# schematic.net
KiCad netlist of a schematic drawn in Altium Designer
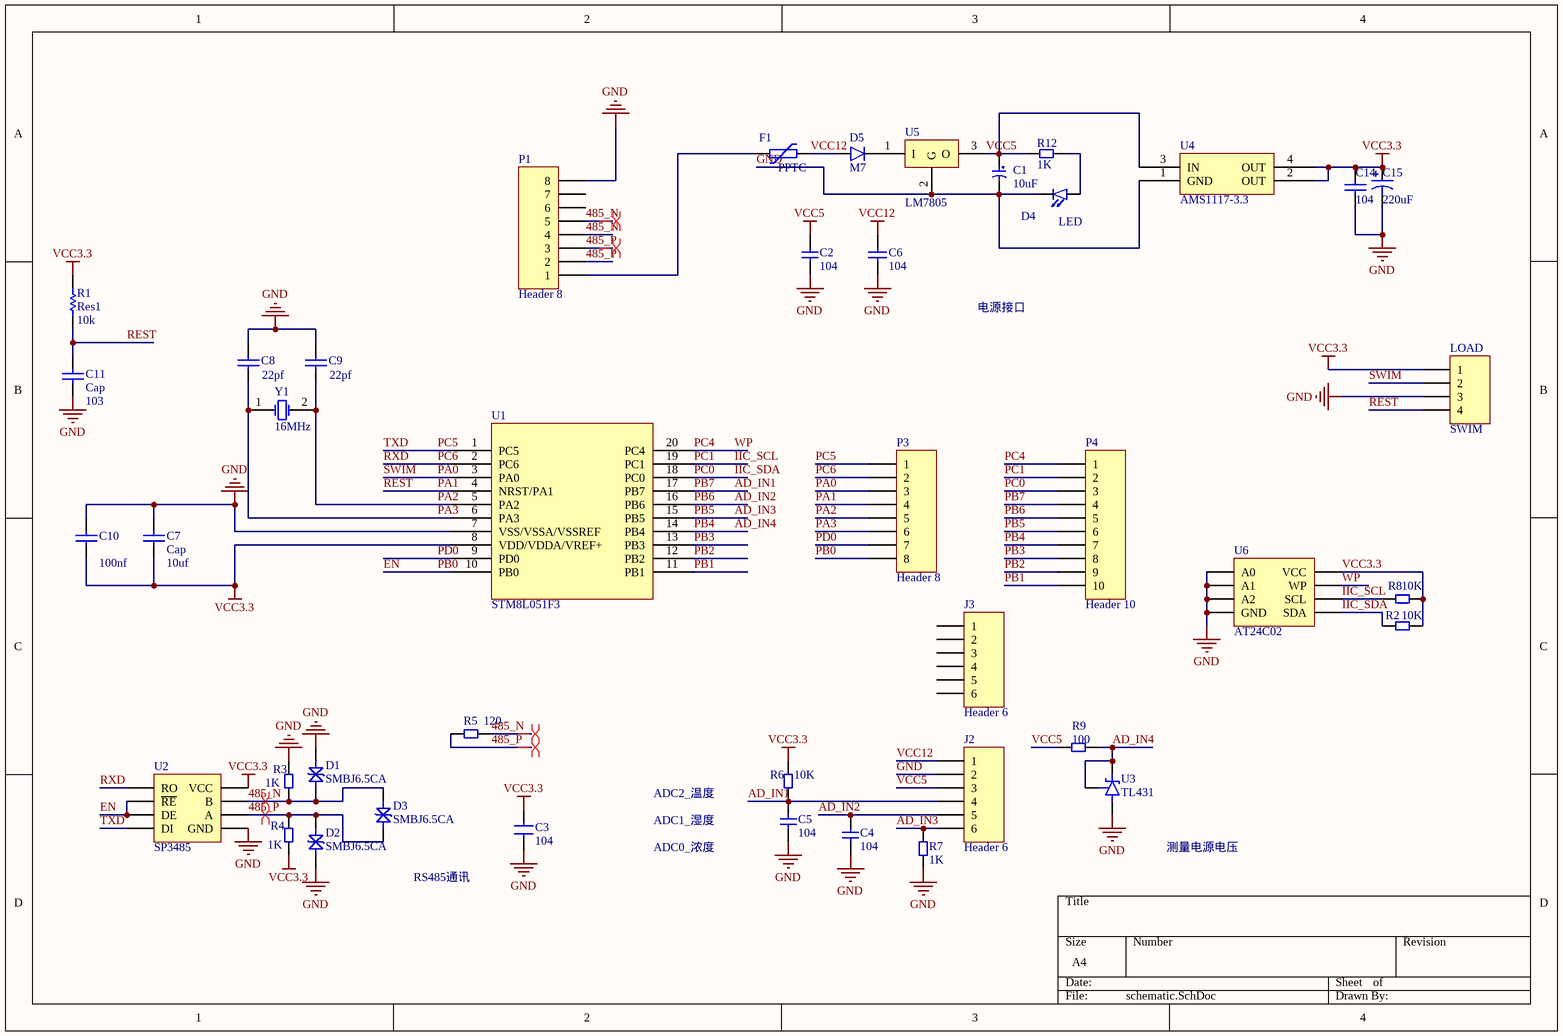
[diagram p0: schematic.SchDoc]

(export (version "E")
  (design (tool "Eeschema 10.0.6"))
  (components
    (comp (ref "C1") (value "10uF") (footprint "1206-d") (libsource (lib "基本") (part "CAP-POL")))
    (comp (ref "C2") (value "104") (footprint "0805") (libsource (lib "基本") (part "CAP")))
    (comp (ref "C3") (value "104") (footprint "0805") (libsource (lib "基本") (part "Cap")))
    (comp (ref "C4") (value "104") (footprint "0805") (libsource (lib "基本") (part "CAP")))
    (comp (ref "C5") (value "104") (footprint "0805") (libsource (lib "基本") (part "CAP")))
    (comp (ref "C6") (value "104") (footprint "0805C") (libsource (lib "basic") (part "CAP")))
    (comp (ref "C7")
      (value "Cap")
      (footprint "1206-D")
      (description "Capacitor")
      (fields (field (name "ALTIUM_VALUE") "10uf") (field (name "PUBLISHER") "Altium Limited"))
      (libsource (lib "Miscellaneous Devices") (part "Cap"))
    )
    (comp (ref "C8")
      (value "22pf")
      (footprint "6-0805_N")
      (description "Capacitor")
      (fields (field (name "Comment") "Cap") (field (name "PUBLISHER") "Altium Limited"))
      (libsource (lib "Miscellaneous Devices") (part "Cap"))
    )
    (comp (ref "C9")
      (value "22pf")
      (footprint "6-0805_N")
      (description "Capacitor")
      (fields (field (name "Comment") "Cap") (field (name "PUBLISHER") "Altium Limited"))
      (libsource (lib "Miscellaneous Devices") (part "Cap"))
    )
    (comp (ref "C10")
      (value "100nf")
      (footprint "0805")
      (description "Capacitor")
      (fields (field (name "Comment") "Cap") (field (name "PUBLISHER") "Altium Limited"))
      (libsource (lib "Miscellaneous Devices") (part "Cap"))
    )
    (comp (ref "C11")
      (value "Cap")
      (footprint "6-0805_N")
      (description "Capacitor")
      (fields (field (name "ALTIUM_VALUE") "103") (field (name "PUBLISHER") "Altium Limited"))
      (libsource (lib "Miscellaneous Devices") (part "Cap"))
    )
    (comp (ref "C14")
      (value "104")
      (footprint "0805")
      (description "Capacitor")
      (fields (field (name "Comment") "Cap") (field (name "PUBLISHER") "Altium Limited"))
      (libsource (lib "Miscellaneous Devices") (part "Cap"))
    )
    (comp (ref "C15")
      (value "220uF")
      (footprint "1206")
      (description "Polarized Capacitor (Radial)")
      (fields (field (name "Comment") "Cap Pol1") (field (name "PUBLISHER") "Altium Limited"))
      (libsource (lib "Miscellaneous Devices") (part "Cap Pol1"))
    )
    (comp (ref "D1") (value "SMBJ6.5CA") (footprint "smb do214aa") (libsource (lib "基本") (part "SMBJ6.5CA")))
    (comp (ref "D2") (value "SMBJ6.5CA") (footprint "smb do214aa") (libsource (lib "基本") (part "SMBJ6.5CA")))
    (comp (ref "D3") (value "SMBJ6.5CA") (footprint "smb do214aa") (libsource (lib "基本") (part "SMBJ6.5CA")))
    (comp (ref "D4") (value "LED") (footprint "0805-D") (libsource (lib "基本") (part "LED")))
    (comp (ref "D5") (value "M7") (footprint "SMA (DO-214AC)") (libsource (lib "基本元件") (part "M7")))
    (comp (ref "F1") (value "PPTC") (footprint "1206") (libsource (lib "基本") (part "PPTC")))
    (comp (ref "J2")
      (value "Header 6")
      (footprint "HDR1X6")
      (description "Header, 6-Pin")
      (fields (field (name "PUBLISHER") "Altium Limited"))
      (libsource (lib "Miscellaneous Connectors") (part "Header 6"))
    )
    (comp (ref "J3")
      (value "Header 6")
      (footprint "HDR1X6")
      (description "Header, 6-Pin")
      (fields (field (name "PUBLISHER") "Altium Limited"))
      (libsource (lib "Miscellaneous Connectors") (part "Header 6"))
    )
    (comp (ref "LOAD")
      (value "SWIM")
      (footprint "HDR1X4")
      (description "Header, 4-Pin")
      (fields (field (name "PUBLISHER") "Altium Limited"))
      (libsource (lib "Miscellaneous Connectors") (part "Header 4"))
    )
    (comp (ref "P1")
      (value "Header 8")
      (footprint "RJ45")
      (description "Header, 8-Pin")
      (fields (field (name "PUBLISHER") "Altium Limited"))
      (libsource (lib "Miscellaneous Connectors") (part "Header 8"))
    )
    (comp (ref "P3")
      (value "Header 8")
      (footprint "HDR1X8")
      (description "Header, 8-Pin")
      (fields (field (name "PUBLISHER") "Altium Limited"))
      (libsource (lib "") (part "Header 8_1"))
    )
    (comp (ref "P4")
      (value "Header 10")
      (footprint "HDR1X10")
      (description "Header, 10-Pin")
      (fields (field (name "PUBLISHER") "Altium Limited"))
      (libsource (lib "Miscellaneous Connectors") (part "Header 10"))
    )
    (comp (ref "R1")
      (value "Res1")
      (footprint "6-0805_N")
      (description "Resistor")
      (fields (field (name "ALTIUM_VALUE") "10k") (field (name "PUBLISHER") "Altium Limited"))
      (libsource (lib "Miscellaneous Devices") (part "Res1"))
    )
    (comp (ref "R2") (value "10K") (footprint "0805") (libsource (lib "基本") (part "Res")))
    (comp (ref "R3") (value "1K") (footprint "0805") (libsource (lib "基本") (part "Res")))
    (comp (ref "R4") (value "1K") (footprint "0805") (libsource (lib "基本") (part "Res")))
    (comp (ref "R5") (value "120") (footprint "0805") (libsource (lib "基本") (part "Res")))
    (comp (ref "R6") (value "10K") (footprint "0805") (libsource (lib "基本") (part "Res")))
    (comp (ref "R7") (value "1K") (footprint "0805") (libsource (lib "基本") (part "Res")))
    (comp (ref "R8") (value "10K") (footprint "0805") (libsource (lib "基本") (part "Res")))
    (comp (ref "R9") (value "100") (footprint "0805") (libsource (lib "基本") (part "Res")))
    (comp (ref "R12") (value "1K") (footprint "0805") (libsource (lib "基本") (part "Res")))
    (comp (ref "U1")
      (value "STM8L051F3")
      (footprint "SOP20")
      (libsource (lib "zs_sener_lib") (part "STM8L051F3"))
    )
    (comp (ref "U2") (value "SP3485") (footprint "油烟采集模块:SOP8") (libsource (lib "常用数字芯片") (part "SP3485")))
    (comp (ref "U3") (value "TL431") (footprint "sot-23") (libsource (lib "电源类") (part "TL431")))
    (comp (ref "U4")
      (value "AMS1117-3.3")
      (footprint "SOT-223")
      (libsource (lib "AMS1117-3.3") (part "AMS1117-3.3"))
    )
    (comp (ref "U5") (value "LM7805") (footprint "to-220") (libsource (lib "电源类") (part "LM7805")))
    (comp (ref "U6") (value "AT24C02") (footprint "油烟采集模块:sop8") (libsource (lib "常用数字芯片") (part "AT24C02")))
    (comp (ref "Y1")
      (value "16MHz")
      (footprint "Y2")
      (description "Crystal Oscillator")
      (fields (field (name "PUBLISHER") "Altium Limited"))
      (libsource (lib "Miscellaneous Devices") (part "XTAL"))
    )
  )
  (nets
    (net (code "1") (name "/485_N") (class "Default")
      (node (ref "D1") (pin "2") (pinfunction "2_2") (pintype "passive"))
      (node (ref "D3") (pin "1") (pinfunction "1_1") (pintype "passive"))
      (node (ref "P1") (pin "4") (pinfunction "4_4") (pintype "passive"))
      (node (ref "P1") (pin "5") (pinfunction "5_5") (pintype "passive"))
      (node (ref "R3") (pin "1") (pinfunction "1_1") (pintype "passive"))
      (node (ref "R5") (pin "1") (pinfunction "1_1") (pintype "passive"))
      (node (ref "U2") (pin "7") (pinfunction "B_7") (pintype "passive"))
    )
    (net (code "2") (name "/485_P") (class "Default")
      (node (ref "D2") (pin "1") (pinfunction "1_1") (pintype "passive"))
      (node (ref "D3") (pin "2") (pinfunction "2_2") (pintype "passive"))
      (node (ref "P1") (pin "2") (pinfunction "2_2") (pintype "passive"))
      (node (ref "P1") (pin "3") (pinfunction "3_3") (pintype "passive"))
      (node (ref "R4") (pin "2") (pinfunction "2_2") (pintype "passive"))
      (node (ref "R5") (pin "2") (pinfunction "2_2") (pintype "passive"))
      (node (ref "U2") (pin "6") (pinfunction "A_6") (pintype "passive"))
    )
    (net (code "3") (name "/AD_IN1") (class "Default")
      (node (ref "C5") (pin "2") (pinfunction "2_2") (pintype "passive"))
      (node (ref "J2") (pin "4") (pinfunction "4_4") (pintype "passive"))
      (node (ref "P4") (pin "4") (pinfunction "4_4") (pintype "passive"))
      (node (ref "R6") (pin "1") (pinfunction "1_1") (pintype "passive"))
      (node (ref "U1") (pin "17") (pinfunction "PB7_17") (pintype "passive"))
    )
    (net (code "4") (name "/AD_IN2") (class "Default")
      (node (ref "C4") (pin "2") (pinfunction "2_2") (pintype "passive"))
      (node (ref "J2") (pin "5") (pinfunction "5_5") (pintype "passive"))
      (node (ref "P4") (pin "5") (pinfunction "5_5") (pintype "passive"))
      (node (ref "U1") (pin "16") (pinfunction "PB6_16") (pintype "passive"))
    )
    (net (code "5") (name "/AD_IN3") (class "Default")
      (node (ref "J2") (pin "6") (pinfunction "6_6") (pintype "passive"))
      (node (ref "P4") (pin "6") (pinfunction "6_6") (pintype "passive"))
      (node (ref "R7") (pin "2") (pinfunction "2_2") (pintype "passive"))
      (node (ref "U1") (pin "15") (pinfunction "PB5_15") (pintype "passive"))
    )
    (net (code "6") (name "/AD_IN4") (class "Default")
      (node (ref "P4") (pin "7") (pinfunction "7_7") (pintype "passive"))
      (node (ref "R9") (pin "2") (pinfunction "2_2") (pintype "passive"))
      (node (ref "U1") (pin "14") (pinfunction "PB4_14") (pintype "passive"))
      (node (ref "U3") (pin "1") (pinfunction "1_1") (pintype "passive"))
      (node (ref "U3") (pin "2") (pinfunction "2_2") (pintype "passive"))
    )
    (net (code "7") (name "/EN") (class "Default")
      (node (ref "P3") (pin "8") (pinfunction "8_8") (pintype "passive"))
      (node (ref "U1") (pin "10") (pinfunction "PB0_10") (pintype "passive"))
      (node (ref "U2") (pin "2") (pinfunction "~{RE}_2") (pintype "passive"))
      (node (ref "U2") (pin "3") (pinfunction "DE_3") (pintype "passive"))
    )
    (net (code "8") (name "/IIC_SCL") (class "Default")
      (node (ref "P4") (pin "2") (pinfunction "2_2") (pintype "passive"))
      (node (ref "R8") (pin "1") (pinfunction "1_1") (pintype "passive"))
      (node (ref "U1") (pin "19") (pinfunction "PC1_19") (pintype "passive"))
      (node (ref "U6") (pin "6") (pinfunction "SCL_6") (pintype "passive"))
    )
    (net (code "9") (name "/IIC_SDA") (class "Default")
      (node (ref "P4") (pin "3") (pinfunction "3_3") (pintype "passive"))
      (node (ref "R2") (pin "1") (pinfunction "1_1") (pintype "passive"))
      (node (ref "U1") (pin "18") (pinfunction "PC0_18") (pintype "passive"))
      (node (ref "U6") (pin "5") (pinfunction "SDA_5") (pintype "passive"))
    )
    (net (code "10") (name "/PA0") (class "Default")
      (node (ref "LOAD") (pin "2") (pinfunction "2_2") (pintype "passive"))
      (node (ref "P3") (pin "3") (pinfunction "3_3") (pintype "passive"))
      (node (ref "U1") (pin "3") (pinfunction "PA0_3") (pintype "passive"))
    )
    (net (code "11") (name "/PA1") (class "Default")
      (node (ref "C11") (pin "2") (pinfunction "2_2") (pintype "passive"))
      (node (ref "LOAD") (pin "4") (pinfunction "4_4") (pintype "passive"))
      (node (ref "P3") (pin "4") (pinfunction "4_4") (pintype "passive"))
      (node (ref "R1") (pin "1") (pinfunction "1_1") (pintype "passive"))
      (node (ref "U1") (pin "4") (pinfunction "NRST/PA1_4") (pintype "passive"))
    )
    (net (code "12") (name "/PA2") (class "Default")
      (node (ref "C9") (pin "2") (pinfunction "2_2") (pintype "passive"))
      (node (ref "P3") (pin "5") (pinfunction "5_5") (pintype "passive"))
      (node (ref "U1") (pin "5") (pinfunction "PA2_5") (pintype "passive"))
      (node (ref "Y1") (pin "2") (pinfunction "OSC2_2") (pintype "passive"))
    )
    (net (code "13") (name "/PA3") (class "Default")
      (node (ref "C8") (pin "1") (pinfunction "1_1") (pintype "passive"))
      (node (ref "P3") (pin "6") (pinfunction "6_6") (pintype "passive"))
      (node (ref "U1") (pin "6") (pinfunction "PA3_6") (pintype "passive"))
      (node (ref "Y1") (pin "1") (pinfunction "OSC1_1") (pintype "passive"))
    )
    (net (code "14") (name "/PB1") (class "Default")
      (node (ref "P4") (pin "10") (pinfunction "10_10") (pintype "passive"))
      (node (ref "U1") (pin "11") (pinfunction "PB1_11") (pintype "passive"))
    )
    (net (code "15") (name "/PB2") (class "Default")
      (node (ref "P4") (pin "9") (pinfunction "9_9") (pintype "passive"))
      (node (ref "U1") (pin "12") (pinfunction "PB2_12") (pintype "passive"))
    )
    (net (code "16") (name "/PB3") (class "Default")
      (node (ref "P4") (pin "8") (pinfunction "8_8") (pintype "passive"))
      (node (ref "U1") (pin "13") (pinfunction "PB3_13") (pintype "passive"))
    )
    (net (code "17") (name "/PC4") (class "Default")
      (node (ref "P4") (pin "1") (pinfunction "1_1") (pintype "passive"))
      (node (ref "U1") (pin "20") (pinfunction "PC4_20") (pintype "passive"))
      (node (ref "U6") (pin "7") (pinfunction "WP_7") (pintype "passive"))
    )
    (net (code "18") (name "/PC5") (class "Default")
      (node (ref "P3") (pin "1") (pinfunction "1_1") (pintype "passive"))
      (node (ref "U1") (pin "1") (pinfunction "PC5_1") (pintype "passive"))
      (node (ref "U2") (pin "4") (pinfunction "DI_4") (pintype "passive"))
    )
    (net (code "19") (name "/PC6") (class "Default")
      (node (ref "P3") (pin "2") (pinfunction "2_2") (pintype "passive"))
      (node (ref "U1") (pin "2") (pinfunction "PC6_2") (pintype "passive"))
      (node (ref "U2") (pin "1") (pinfunction "RO_1") (pintype "passive"))
    )
    (net (code "20") (name "/PD0") (class "Default")
      (node (ref "P3") (pin "7") (pinfunction "7_7") (pintype "passive"))
      (node (ref "U1") (pin "9") (pinfunction "PD0_9") (pintype "passive"))
    )
    (net (code "21") (name "GND") (class "Default")
      (node (ref "C1") (pin "1") (pinfunction "1_1") (pintype "passive"))
      (node (ref "C10") (pin "2") (pinfunction "2_2") (pintype "passive"))
      (node (ref "C11") (pin "1") (pinfunction "1_1") (pintype "passive"))
      (node (ref "C14") (pin "1") (pinfunction "1_1") (pintype "passive"))
      (node (ref "C15") (pin "2") (pinfunction "2_2") (pintype "passive"))
      (node (ref "C2") (pin "1") (pinfunction "1_1") (pintype "passive"))
      (node (ref "C3") (pin "1") (pinfunction "1_1") (pintype "passive"))
      (node (ref "C4") (pin "1") (pinfunction "1_1") (pintype "passive"))
      (node (ref "C5") (pin "1") (pinfunction "1_1") (pintype "passive"))
      (node (ref "C6") (pin "1") (pinfunction "1_1") (pintype "passive"))
      (node (ref "C7") (pin "1") (pinfunction "1_1") (pintype "passive"))
      (node (ref "C8") (pin "2") (pinfunction "2_2") (pintype "passive"))
      (node (ref "C9") (pin "1") (pinfunction "1_1") (pintype "passive"))
      (node (ref "D1") (pin "1") (pinfunction "1_1") (pintype "passive"))
      (node (ref "D2") (pin "2") (pinfunction "2_2") (pintype "passive"))
      (node (ref "D4") (pin "2") (pinfunction "2_2") (pintype "passive"))
      (node (ref "J2") (pin "2") (pinfunction "2_2") (pintype "passive"))
      (node (ref "LOAD") (pin "3") (pinfunction "3_3") (pintype "passive"))
      (node (ref "P1") (pin "8") (pinfunction "8_8") (pintype "passive"))
      (node (ref "R3") (pin "2") (pinfunction "2_2") (pintype "passive"))
      (node (ref "R7") (pin "1") (pinfunction "1_1") (pintype "passive"))
      (node (ref "U1") (pin "7") (pinfunction "VSS/VSSA/VSSREF_7") (pintype "passive"))
      (node (ref "U2") (pin "5") (pinfunction "GND_5") (pintype "passive"))
      (node (ref "U3") (pin "3") (pinfunction "3_3") (pintype "passive"))
      (node (ref "U4") (pin "1") (pinfunction "GND_1") (pintype "passive"))
      (node (ref "U5") (pin "2") (pinfunction "G_2") (pintype "passive"))
      (node (ref "U6") (pin "1") (pinfunction "A0_1") (pintype "passive"))
      (node (ref "U6") (pin "2") (pinfunction "A1_2") (pintype "passive"))
      (node (ref "U6") (pin "3") (pinfunction "A2_3") (pintype "passive"))
      (node (ref "U6") (pin "4") (pinfunction "GND_4") (pintype "passive"))
    )
    (net (code "22") (name "Net-(D4-Pad1)") (class "Default")
      (node (ref "D4") (pin "1") (pinfunction "1_1") (pintype "passive"))
      (node (ref "R12") (pin "2") (pinfunction "2_2") (pintype "passive"))
    )
    (net (code "23") (name "Net-(D5--)") (class "Default")
      (node (ref "D5") (pin "1") (pinfunction "-_1") (pintype "passive"))
      (node (ref "U5") (pin "1") (pinfunction "I_1") (pintype "passive"))
    )
    (net (code "24") (name "Net-(F1-Pad1)") (class "Default")
      (node (ref "F1") (pin "1") (pinfunction "1_1") (pintype "passive"))
      (node (ref "P1") (pin "1") (pinfunction "1_1") (pintype "passive"))
    )
    (net (code "25") (name "VCC3.3") (class "Default")
      (node (ref "C10") (pin "1") (pinfunction "1_1") (pintype "passive"))
      (node (ref "C14") (pin "2") (pinfunction "2_2") (pintype "passive"))
      (node (ref "C15") (pin "1") (pinfunction "1_1") (pintype "passive"))
      (node (ref "C3") (pin "2") (pinfunction "2_2") (pintype "passive"))
      (node (ref "C7") (pin "2") (pinfunction "2_2") (pintype "passive"))
      (node (ref "LOAD") (pin "1") (pinfunction "1_1") (pintype "passive"))
      (node (ref "R1") (pin "2") (pinfunction "2_2") (pintype "passive"))
      (node (ref "R2") (pin "2") (pinfunction "2_2") (pintype "passive"))
      (node (ref "R4") (pin "1") (pinfunction "1_1") (pintype "passive"))
      (node (ref "R6") (pin "2") (pinfunction "2_2") (pintype "passive"))
      (node (ref "R8") (pin "2") (pinfunction "2_2") (pintype "passive"))
      (node (ref "U1") (pin "8") (pinfunction "VDD/VDDA/VREF+_8") (pintype "passive"))
      (node (ref "U2") (pin "8") (pinfunction "VCC_8") (pintype "passive"))
      (node (ref "U4") (pin "2") (pinfunction "OUT_2") (pintype "passive"))
      (node (ref "U4") (pin "4") (pinfunction "OUT_4") (pintype "passive"))
      (node (ref "U6") (pin "8") (pinfunction "VCC_8") (pintype "passive"))
    )
    (net (code "26") (name "VCC5") (class "Default")
      (node (ref "C1") (pin "2") (pinfunction "2_2") (pintype "passive"))
      (node (ref "C2") (pin "2") (pinfunction "2_2") (pintype "passive"))
      (node (ref "J2") (pin "3") (pinfunction "3_3") (pintype "passive"))
      (node (ref "R12") (pin "1") (pinfunction "1_1") (pintype "passive"))
      (node (ref "R9") (pin "1") (pinfunction "1_1") (pintype "passive"))
      (node (ref "U4") (pin "3") (pinfunction "IN_3") (pintype "passive"))
      (node (ref "U5") (pin "3") (pinfunction "O_3") (pintype "passive"))
    )
    (net (code "27") (name "VCC12") (class "Default")
      (node (ref "C6") (pin "2") (pinfunction "2_2") (pintype "passive"))
      (node (ref "D5") (pin "2") (pinfunction "+_2") (pintype "passive"))
      (node (ref "F1") (pin "2") (pinfunction "2_2") (pintype "passive"))
      (node (ref "J2") (pin "1") (pinfunction "1_1") (pintype "passive"))
    )
    (net (code "28") (name "unconnected-(J3-Pad1)") (class "Default")
      (node (ref "J3") (pin "1") (pinfunction "1_1") (pintype "passive"))
    )
    (net (code "29") (name "unconnected-(J3-Pad2)") (class "Default")
      (node (ref "J3") (pin "2") (pinfunction "2_2") (pintype "passive"))
    )
    (net (code "30") (name "unconnected-(J3-Pad3)") (class "Default")
      (node (ref "J3") (pin "3") (pinfunction "3_3") (pintype "passive"))
    )
    (net (code "31") (name "unconnected-(J3-Pad4)") (class "Default")
      (node (ref "J3") (pin "4") (pinfunction "4_4") (pintype "passive"))
    )
    (net (code "32") (name "unconnected-(J3-Pad5)") (class "Default")
      (node (ref "J3") (pin "5") (pinfunction "5_5") (pintype "passive"))
    )
    (net (code "33") (name "unconnected-(J3-Pad6)") (class "Default")
      (node (ref "J3") (pin "6") (pinfunction "6_6") (pintype "passive"))
    )
    (net (code "34") (name "unconnected-(P1-Pad6)") (class "Default")
      (node (ref "P1") (pin "6") (pinfunction "6_6") (pintype "passive"))
    )
    (net (code "35") (name "unconnected-(P1-Pad7)") (class "Default")
      (node (ref "P1") (pin "7") (pinfunction "7_7") (pintype "passive"))
    )
  )
)
